# Parametric_EQ.net
KiCad netlist of a schematic drawn in Altium Designer
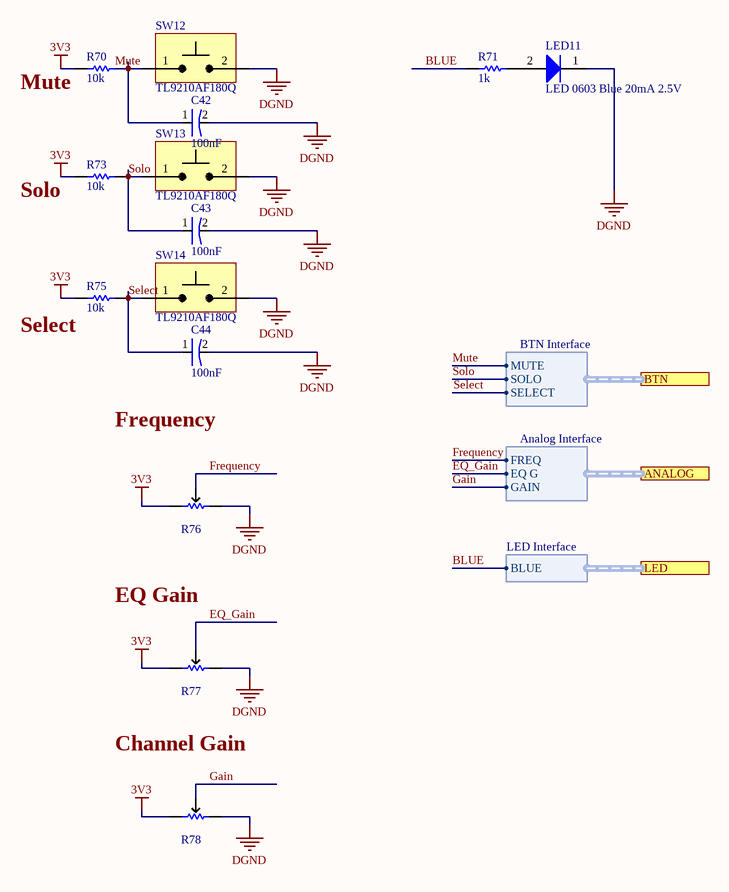
[diagram p0: Parametric EQ.SchDoc]

(export (version "E")
  (design (tool "Eeschema 10.0.6"))
  (components
    (comp (ref "C42")
      (value "100nF")
      (footprint "0402-M")
      (description "CAP-0.1uF-CER-0402-16V-X5R-10%")
      (fields
        (field (name "MANUFACTURER") "Generic")
        (field (name "Comment") "CAP 0.1uF CER 0402 16V X5R 10%")
      )
      (libsource (lib "University of Malta - MEMENTO") (part "Symbol"))
    )
    (comp (ref "C43")
      (value "100nF")
      (footprint "0402-M")
      (description "CAP-0.1uF-CER-0402-16V-X5R-10%")
      (fields
        (field (name "MANUFACTURER") "Generic")
        (field (name "Comment") "CAP 0.1uF CER 0402 16V X5R 10%")
      )
      (libsource (lib "University of Malta - MEMENTO") (part "Symbol"))
    )
    (comp (ref "C44")
      (value "100nF")
      (footprint "0402-M")
      (description "CAP-0.1uF-CER-0402-16V-X5R-10%")
      (fields
        (field (name "MANUFACTURER") "Generic")
        (field (name "Comment") "CAP 0.1uF CER 0402 16V X5R 10%")
      )
      (libsource (lib "University of Malta - MEMENTO") (part "Symbol"))
    )
    (comp (ref "LED11")
      (value "LED 0603 Blue 20mA 2.5V")
      (footprint "VAOL-S6SB4")
      (description "LED-0603-Blue-20mA-2.5V-STOCK")
      (fields
        (field (name "DESIGN ITEM ID") "LED 0603 Blue 20mA 2.5V")
        (field (name "MANUFACTURER") "Generic")
      )
      (libsource (lib "") (part "Symbol_3"))
    )
    (comp (ref "R70")
      (value "10k")
      (footprint "0402-M")
      (description "RES-10k-0402-63mW-5%")
      (fields (field (name "MANUFACTURER") "Generic") (field (name "Comment") "RES 10k 0402 63mW 5%"))
      (libsource (lib "") (part "Symbol_2"))
    )
    (comp (ref "R71")
      (value "1k")
      (footprint "0402-M")
      (description "RES-1k-0402-63mW-1%")
      (fields (field (name "MANUFACTURER") "Generic") (field (name "Comment") "RES 1k 0402 63mW 1%"))
      (libsource (lib "") (part "Symbol_2"))
    )
    (comp (ref "R73")
      (value "10k")
      (footprint "0402-M")
      (description "RES-10k-0402-63mW-5%")
      (fields (field (name "MANUFACTURER") "Generic") (field (name "Comment") "RES 10k 0402 63mW 5%"))
      (libsource (lib "") (part "Symbol_2"))
    )
    (comp (ref "R75")
      (value "10k")
      (footprint "0402-M")
      (description "RES-10k-0402-63mW-5%")
      (fields (field (name "MANUFACTURER") "Generic") (field (name "Comment") "RES 10k 0402 63mW 5%"))
      (libsource (lib "") (part "Symbol_2"))
    )
    (comp (ref "R76")
      (value "P120PK-Y25BR10K")
      (footprint "P120PK-Y25BR10K-Footprint-1")
      (description "Potentiometers 12mm 10K ohm")
      (fields (field (name "TOLERANCE") "20%"))
      (libsource (lib "University of Malta - MEMENTO") (part "P120PK-Y25BR10K"))
    )
    (comp (ref "R77")
      (value "P120PK-Y25BR10K")
      (footprint "P120PK-Y25BR10K-Footprint-1")
      (description "Potentiometers 12mm 10K ohm")
      (fields (field (name "TOLERANCE") "20%"))
      (libsource (lib "University of Malta - MEMENTO") (part "P120PK-Y25BR10K"))
    )
    (comp (ref "R78")
      (value "P120PK-Y25BR10K")
      (footprint "P120PK-Y25BR10K-Footprint-1")
      (description "Potentiometers 12mm 10K ohm")
      (fields (field (name "TOLERANCE") "20%"))
      (libsource (lib "University of Malta - MEMENTO") (part "P120PK-Y25BR10K"))
    )
    (comp (ref "SW12")
      (value "TL9210AF180Q")
      (footprint "TL9210")
      (description "SWITCH MOM SMD SPST 50MA 12V Soft Tact")
      (fields (field (name "MANUFACTURER") "E-Switch") (field (name "DESIGN ITEM ID") "TL9210AF180Q"))
      (libsource (lib "") (part "Symbol_1"))
    )
    (comp (ref "SW13")
      (value "TL9210AF180Q")
      (footprint "TL9210")
      (description "SWITCH MOM SMD SPST 50MA 12V Soft Tact")
      (fields (field (name "MANUFACTURER") "E-Switch") (field (name "DESIGN ITEM ID") "TL9210AF180Q"))
      (libsource (lib "") (part "Symbol_1"))
    )
    (comp (ref "SW14")
      (value "TL9210AF180Q")
      (footprint "TL9210")
      (description "SWITCH MOM SMD SPST 50MA 12V Soft Tact")
      (fields (field (name "MANUFACTURER") "E-Switch") (field (name "DESIGN ITEM ID") "TL9210AF180Q"))
      (libsource (lib "") (part "Symbol_1"))
    )
  )
  (nets
    (net (code "5") (name "/BLUE") (class "Default")
      (node (ref "R71") (pin "1") (pinfunction "1_1") (pintype "passive"))
    )
    (net (code "6") (name "/EQ_Gain") (class "Default")
      (node (ref "R77") (pin "2") (pinfunction "2_2") (pintype "passive"))
    )
    (net (code "7") (name "/Frequency") (class "Default")
      (node (ref "R76") (pin "2") (pinfunction "2_2") (pintype "passive"))
    )
    (net (code "8") (name "/Gain") (class "Default")
      (node (ref "R78") (pin "2") (pinfunction "2_2") (pintype "passive"))
    )
    (net (code "9") (name "/Mute") (class "Default")
      (node (ref "C42") (pin "1") (pinfunction "Anode_1") (pintype "passive"))
      (node (ref "R70") (pin "2") (pinfunction "2_2") (pintype "passive"))
      (node (ref "SW12") (pin "1") (pinfunction "1_1") (pintype "passive"))
    )
    (net (code "10") (name "/Select") (class "Default")
      (node (ref "C44") (pin "1") (pinfunction "Anode_1") (pintype "passive"))
      (node (ref "R75") (pin "2") (pinfunction "2_2") (pintype "passive"))
      (node (ref "SW14") (pin "1") (pinfunction "1_1") (pintype "passive"))
    )
    (net (code "11") (name "/Solo") (class "Default")
      (node (ref "C43") (pin "1") (pinfunction "Anode_1") (pintype "passive"))
      (node (ref "R73") (pin "2") (pinfunction "2_2") (pintype "passive"))
      (node (ref "SW13") (pin "1") (pinfunction "1_1") (pintype "passive"))
    )
    (net (code "15") (name "3V3") (class "Default")
      (node (ref "R70") (pin "1") (pinfunction "1_1") (pintype "passive"))
      (node (ref "R73") (pin "1") (pinfunction "1_1") (pintype "passive"))
      (node (ref "R75") (pin "1") (pinfunction "1_1") (pintype "passive"))
      (node (ref "R76") (pin "1") (pinfunction "1_1") (pintype "passive"))
      (node (ref "R77") (pin "1") (pinfunction "1_1") (pintype "passive"))
      (node (ref "R78") (pin "1") (pinfunction "1_1") (pintype "passive"))
    )
    (net (code "16") (name "DGND") (class "Default")
      (node (ref "C42") (pin "2") (pinfunction "Cathode_2") (pintype "passive"))
      (node (ref "C43") (pin "2") (pinfunction "Cathode_2") (pintype "passive"))
      (node (ref "C44") (pin "2") (pinfunction "Cathode_2") (pintype "passive"))
      (node (ref "LED11") (pin "1") (pinfunction "1_1") (pintype "passive"))
      (node (ref "R76") (pin "3") (pinfunction "3_3") (pintype "passive"))
      (node (ref "R77") (pin "3") (pinfunction "3_3") (pintype "passive"))
      (node (ref "R78") (pin "3") (pinfunction "3_3") (pintype "passive"))
      (node (ref "SW12") (pin "2") (pinfunction "2_2") (pintype "passive"))
      (node (ref "SW13") (pin "2") (pinfunction "2_2") (pintype "passive"))
      (node (ref "SW14") (pin "2") (pinfunction "2_2") (pintype "passive"))
    )
    (net (code "17") (name "Net-(LED11-Pad2)") (class "Default")
      (node (ref "LED11") (pin "2") (pinfunction "2_2") (pintype "passive"))
      (node (ref "R71") (pin "2") (pinfunction "2_2") (pintype "passive"))
    )
  )
)
